# tvbgone3.net
KiCad netlist of a schematic drawn in EAGLE
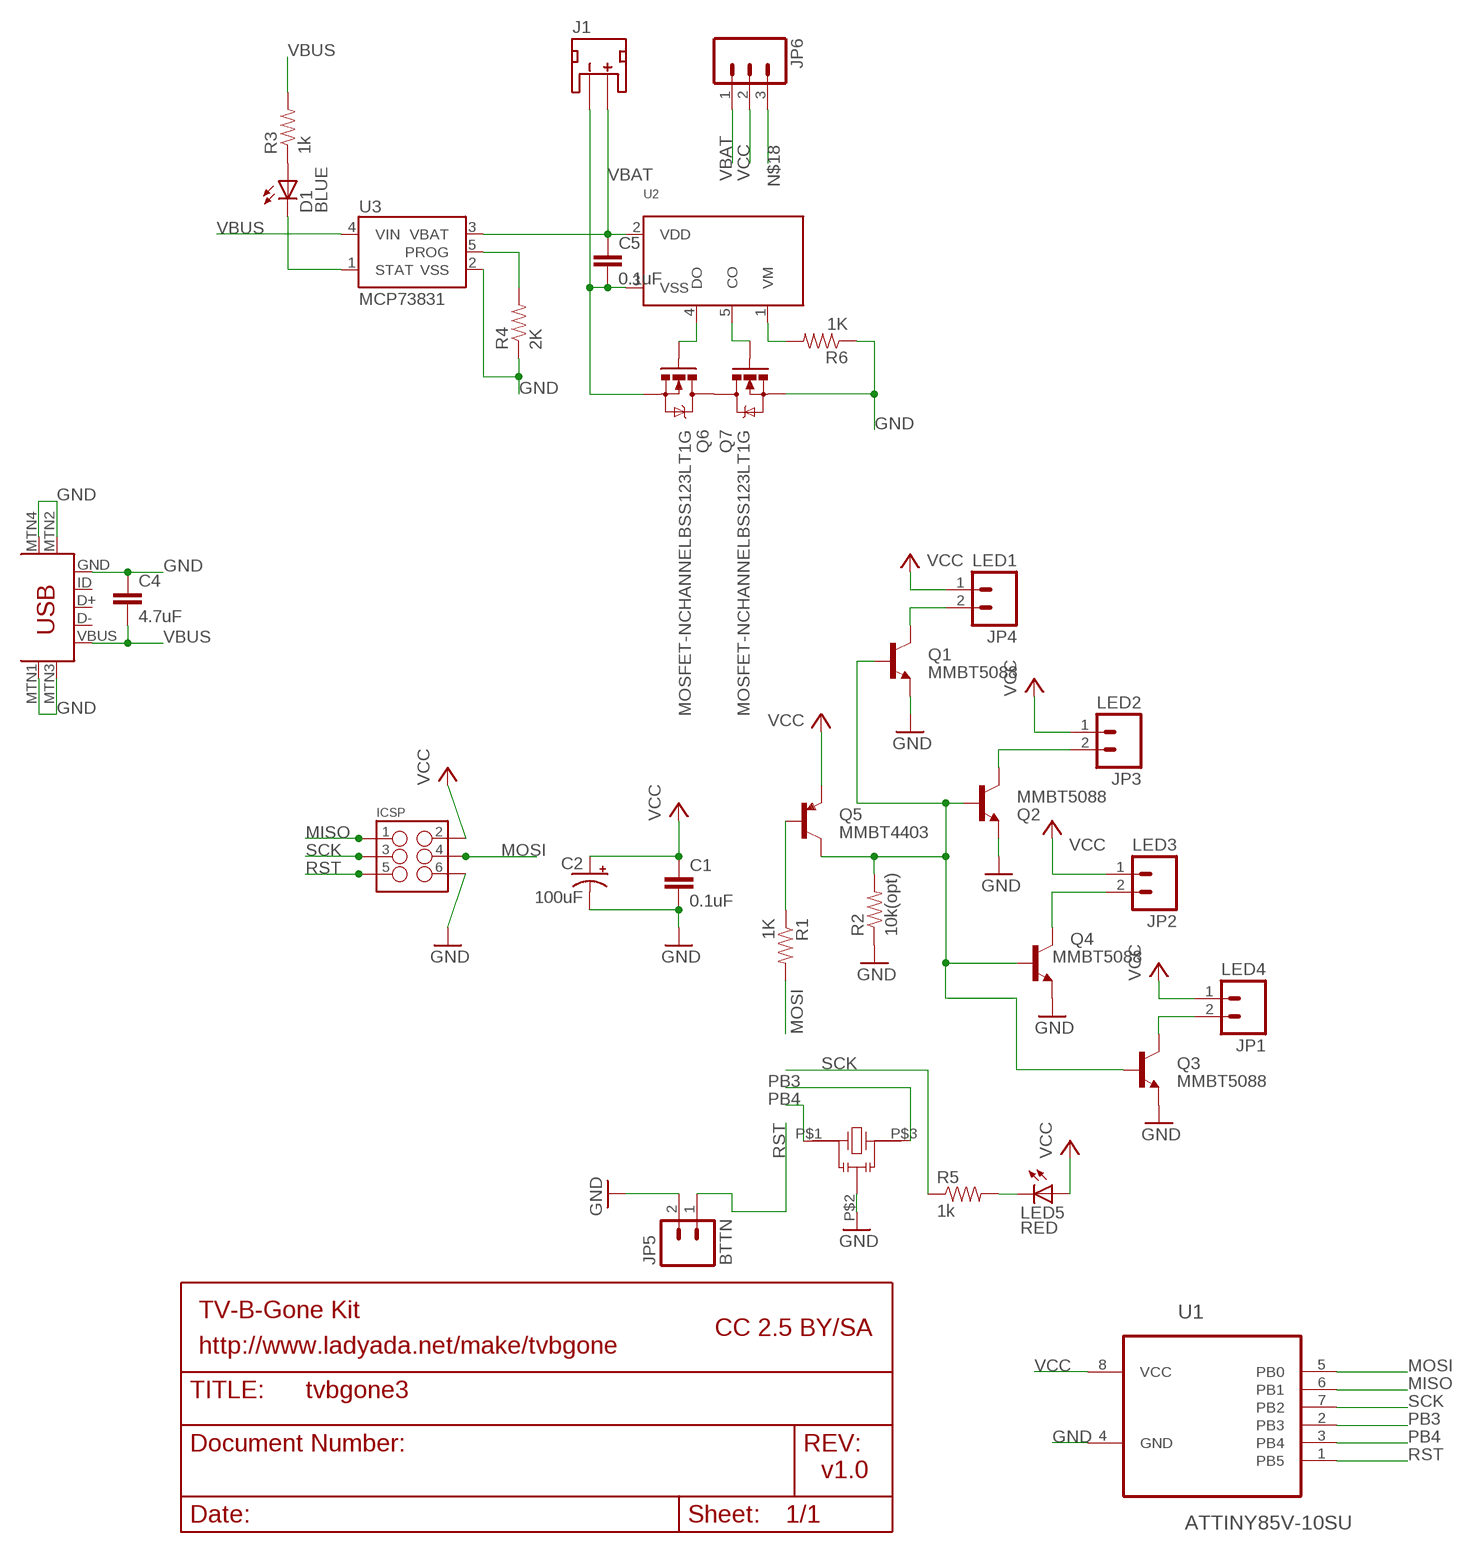
[diagram p0: schematic, sheet 1]

(export (version "E")
  (design (tool "Eeschema 10.0.6"))
  (components
    (comp (ref "C1")
      (value "0.1uF")
      (footprint "eagle-import:0603-CAP")
      (libsource (lib "eagle-import") (part "0.1UF-25V-5%(0603)"))
    )
    (comp (ref "C2")
      (value "100uF")
      (footprint "eagle-import:PANASONIC_C")
      (libsource (lib "eagle-import") (part "CAP_POLC"))
    )
    (comp (ref "C4")
      (value "4.7uF")
      (footprint "eagle-import:0603-CAP")
      (libsource (lib "eagle-import") (part "0.22UF50V-20%,+80%(0603)"))
    )
    (comp (ref "C5")
      (value "0.1uF")
      (footprint "eagle-import:0603-CAP")
      (libsource (lib "eagle-import") (part "0.22UF50V-20%,+80%(0603)"))
    )
    (comp (ref "D1")
      (value "BLUE")
      (footprint "eagle-import:LED-0603")
      (libsource (lib "eagle-import") (part "LED-BLUE0603"))
    )
    (comp (ref "ICSP")
      (value "M03X2SMT")
      (footprint "eagle-import:2X3_SMT_POSTS")
      (libsource (lib "eagle-import") (part "M03X2SMT"))
    )
    (comp (ref "J1")
      (value "JST_2MM_MALE")
      (footprint "eagle-import:JST-2-SMD")
      (libsource (lib "eagle-import") (part "JST_2MM_MALE"))
    )
    (comp (ref "JP1")
      (value "LED4")
      (footprint "eagle-import:1X02_LONGPADS")
      (libsource (lib "eagle-import") (part "M02PTH3"))
    )
    (comp (ref "JP2")
      (value "LED3")
      (footprint "eagle-import:1X02_LONGPADS")
      (libsource (lib "eagle-import") (part "M02PTH3"))
    )
    (comp (ref "JP3")
      (value "LED2")
      (footprint "eagle-import:1X02_LONGPADS")
      (libsource (lib "eagle-import") (part "M02PTH3"))
    )
    (comp (ref "JP4")
      (value "LED1")
      (footprint "eagle-import:1X02_LONGPADS")
      (libsource (lib "eagle-import") (part "M02PTH3"))
    )
    (comp (ref "JP5")
      (value "BTTN")
      (footprint "eagle-import:1X02_LONGPADS")
      (libsource (lib "eagle-import") (part "M02PTH3"))
    )
    (comp (ref "JP6")
      (value "M03SMD_RA_MALE")
      (footprint "eagle-import:1X03_SMD_RA_MALE")
      (libsource (lib "eagle-import") (part "M03SMD_RA_MALE"))
    )
    (comp (ref "LED5")
      (value "RED")
      (footprint "eagle-import:LED-0603")
      (libsource (lib "eagle-import") (part "LED0603"))
    )
    (comp (ref "Q1")
      (value "MMBT5088")
      (footprint "eagle-import:SOT23")
      (libsource (lib "eagle-import") (part "TRANSISTOR_NPNMMBT5088"))
    )
    (comp (ref "Q2")
      (value "MMBT5088")
      (footprint "eagle-import:SOT23")
      (libsource (lib "eagle-import") (part "TRANSISTOR_NPNMMBT5088"))
    )
    (comp (ref "Q3")
      (value "MMBT5088")
      (footprint "eagle-import:SOT23")
      (libsource (lib "eagle-import") (part "TRANSISTOR_NPNMMBT5088"))
    )
    (comp (ref "Q4")
      (value "MMBT5088")
      (footprint "eagle-import:SOT23")
      (libsource (lib "eagle-import") (part "TRANSISTOR_NPNMMBT5088"))
    )
    (comp (ref "Q5")
      (value "MMBT4403")
      (footprint "eagle-import:SOT23")
      (libsource (lib "eagle-import") (part "TRANSISTOR_PNPMMBT4403"))
    )
    (comp (ref "Q6")
      (value "MOSFET-NCHANNELBSS123LT1G")
      (footprint "eagle-import:SOT23")
      (libsource (lib "eagle-import") (part "MOSFET-NCHANNELBSS123LT1G"))
    )
    (comp (ref "Q7")
      (value "MOSFET-NCHANNELBSS123LT1G")
      (footprint "eagle-import:SOT23")
      (libsource (lib "eagle-import") (part "MOSFET-NCHANNELBSS123LT1G"))
    )
    (comp (ref "R1")
      (value "1K")
      (footprint "eagle-import:0603-RES")
      (libsource (lib "eagle-import") (part "2MOHMS-1/10W-1%(0603)"))
    )
    (comp (ref "R2")
      (value "10k(opt)")
      (footprint "eagle-import:0603-RES")
      (libsource (lib "eagle-import") (part "2MOHMS-1/10W-1%(0603)"))
    )
    (comp (ref "R3")
      (value "1k")
      (footprint "eagle-import:0603-RES")
      (libsource (lib "eagle-import") (part "3.3MOHM-1/10W-1%(0603)"))
    )
    (comp (ref "R4")
      (value "2K")
      (footprint "eagle-import:0603-RES")
      (libsource (lib "eagle-import") (part "3.3MOHM-1/10W-1%(0603)"))
    )
    (comp (ref "R5")
      (value "1k")
      (footprint "eagle-import:0603-RES")
      (libsource (lib "eagle-import") (part "2MOHMS-1/10W-1%(0603)"))
    )
    (comp (ref "R6")
      (value "1K")
      (footprint "eagle-import:0603-RES")
      (libsource (lib "eagle-import") (part "3.3MOHM-1/10W-1%(0603)"))
    )
    (comp (ref "U$1")
      (value "CTSCE8M_00G52")
      (footprint "eagle-import:CSTCE")
      (libsource (lib "eagle-import") (part "CTSCE8M_00G52"))
    )
    (comp (ref "U$2")
      (value "USB-MINIB-5PIN")
      (footprint "eagle-import:USB-MINIB")
      (libsource (lib "eagle-import") (part "USB-MINIB-5PIN"))
    )
    (comp (ref "U1")
      (value "ATTINY85V-10SU")
      (footprint "eagle-import:SOIC127P798X216-8N")
      (libsource (lib "eagle-import") (part "ATTINY85V-10SU"))
    )
    (comp (ref "U2")
      (value "S-8241")
      (footprint "eagle-import:SOT23-5L")
      (libsource (lib "eagle-import") (part "S-8241"))
    )
    (comp (ref "U3")
      (value "MCP73831")
      (footprint "eagle-import:SOT23-5")
      (libsource (lib "eagle-import") (part "MCP73831"))
    )
  )
  (nets
    (net (code "1") (name "/MISO") (class "Default")
      (node (ref "ICSP") (pin "1") (pinfunction "1_1") (pintype "bidirectional"))
      (node (ref "U1") (pin "6") (pinfunction "PB1_6") (pintype "bidirectional"))
    )
    (net (code "2") (name "/MOSI") (class "Default")
      (node (ref "ICSP") (pin "4") (pinfunction "4_4") (pintype "bidirectional"))
      (node (ref "R1") (pin "2") (pinfunction "2_2") (pintype "passive"))
      (node (ref "U1") (pin "5") (pinfunction "PB0_5") (pintype "bidirectional"))
    )
    (net (code "3") (name "/N$18") (class "Default")
      (node (ref "JP6") (pin "3") (pinfunction "3_3") (pintype "passive"))
    )
    (net (code "4") (name "/PB3") (class "Default")
      (node (ref "U$1") (pin "P$3") (pinfunction "P$3_P$3") (pintype "bidirectional"))
      (node (ref "U1") (pin "2") (pinfunction "PB3_2") (pintype "bidirectional"))
    )
    (net (code "5") (name "/PB4") (class "Default")
      (node (ref "U$1") (pin "P$1") (pinfunction "P$1_P$1") (pintype "bidirectional"))
      (node (ref "U1") (pin "3") (pinfunction "PB4_3") (pintype "bidirectional"))
    )
    (net (code "6") (name "/RST") (class "Default")
      (node (ref "ICSP") (pin "5") (pinfunction "5_5") (pintype "bidirectional"))
      (node (ref "JP5") (pin "1") (pinfunction "1_1") (pintype "passive"))
      (node (ref "U1") (pin "1") (pinfunction "PB5_1") (pintype "bidirectional"))
    )
    (net (code "7") (name "/SCK") (class "Default")
      (node (ref "ICSP") (pin "3") (pinfunction "3_3") (pintype "bidirectional"))
      (node (ref "R5") (pin "1") (pinfunction "1_1") (pintype "passive"))
      (node (ref "U1") (pin "7") (pinfunction "PB2_7") (pintype "bidirectional"))
    )
    (net (code "8") (name "/VBAT") (class "Default")
      (node (ref "C5") (pin "1") (pinfunction "1_1") (pintype "passive"))
      (node (ref "J1") (pin "2") (pinfunction "+_2") (pintype "bidirectional"))
      (node (ref "JP6") (pin "1") (pinfunction "1_1") (pintype "passive"))
      (node (ref "U2") (pin "2") (pinfunction "VDD_2") (pintype "power_in"))
      (node (ref "U3") (pin "3") (pinfunction "VBAT_3") (pintype "power_in"))
    )
    (net (code "9") (name "/VBUS") (class "Default")
      (node (ref "C4") (pin "2") (pinfunction "2_2") (pintype "passive"))
      (node (ref "R3") (pin "2") (pinfunction "2_2") (pintype "passive"))
      (node (ref "U$2") (pin "VBUS") (pinfunction "VBUS_VBUS") (pintype "bidirectional"))
      (node (ref "U3") (pin "4") (pinfunction "VIN_4") (pintype "power_in"))
    )
    (net (code "10") (name "GND") (class "Default")
      (node (ref "C1") (pin "2") (pinfunction "2_2") (pintype "passive"))
      (node (ref "C2") (pin "-") (pinfunction "-_-") (pintype "passive"))
      (node (ref "C4") (pin "1") (pinfunction "1_1") (pintype "passive"))
      (node (ref "ICSP") (pin "6") (pinfunction "6_6") (pintype "bidirectional"))
      (node (ref "JP5") (pin "2") (pinfunction "2_2") (pintype "passive"))
      (node (ref "Q1") (pin "2") (pinfunction "E_2") (pintype "passive"))
      (node (ref "Q2") (pin "2") (pinfunction "E_2") (pintype "passive"))
      (node (ref "Q3") (pin "2") (pinfunction "E_2") (pintype "passive"))
      (node (ref "Q4") (pin "2") (pinfunction "E_2") (pintype "passive"))
      (node (ref "Q7") (pin "2") (pinfunction "S_2") (pintype "passive"))
      (node (ref "R2") (pin "1") (pinfunction "1_1") (pintype "passive"))
      (node (ref "R4") (pin "1") (pinfunction "1_1") (pintype "passive"))
      (node (ref "R6") (pin "1") (pinfunction "1_1") (pintype "passive"))
      (node (ref "U$1") (pin "P$2") (pinfunction "P$2_P$2") (pintype "bidirectional"))
      (node (ref "U$2") (pin "GND") (pinfunction "GND_GND") (pintype "bidirectional"))
      (node (ref "U$2") (pin "MTN1") (pinfunction "MTN2_MTN1") (pintype "bidirectional"))
      (node (ref "U$2") (pin "MTN2") (pinfunction "MTN3_MTN2") (pintype "bidirectional"))
      (node (ref "U$2") (pin "MTN3") (pinfunction "MTN1_MTN3") (pintype "bidirectional"))
      (node (ref "U$2") (pin "MTN4") (pinfunction "MTN4_MTN4") (pintype "bidirectional"))
      (node (ref "U1") (pin "4") (pinfunction "GND_4") (pintype "passive"))
      (node (ref "U3") (pin "2") (pinfunction "VSS_2") (pintype "power_in"))
    )
    (net (code "11") (name "Net-(D1-PadA)") (class "Default")
      (node (ref "D1") (pin "A") (pinfunction "A_A") (pintype "passive"))
      (node (ref "R3") (pin "1") (pinfunction "1_1") (pintype "passive"))
    )
    (net (code "12") (name "Net-(J1--)") (class "Default")
      (node (ref "C5") (pin "2") (pinfunction "2_2") (pintype "passive"))
      (node (ref "J1") (pin "1") (pinfunction "-_1") (pintype "bidirectional"))
      (node (ref "Q6") (pin "2") (pinfunction "S_2") (pintype "passive"))
      (node (ref "U2") (pin "3") (pinfunction "VSS_3") (pintype "power_in"))
    )
    (net (code "13") (name "Net-(LED5-PadC)") (class "Default")
      (node (ref "LED5") (pin "C") (pinfunction "C_C") (pintype "passive"))
      (node (ref "R5") (pin "2") (pinfunction "2_2") (pintype "passive"))
    )
    (net (code "14") (name "Net-(Q1-B)") (class "Default")
      (node (ref "Q1") (pin "1") (pinfunction "B_1") (pintype "passive"))
      (node (ref "Q2") (pin "1") (pinfunction "B_1") (pintype "passive"))
      (node (ref "Q3") (pin "1") (pinfunction "B_1") (pintype "passive"))
      (node (ref "Q4") (pin "1") (pinfunction "B_1") (pintype "passive"))
      (node (ref "Q5") (pin "3") (pinfunction "C_3") (pintype "passive"))
      (node (ref "R2") (pin "2") (pinfunction "2_2") (pintype "passive"))
    )
    (net (code "15") (name "Net-(Q1-C)") (class "Default")
      (node (ref "JP4") (pin "2") (pinfunction "2_2") (pintype "passive"))
      (node (ref "Q1") (pin "3") (pinfunction "C_3") (pintype "passive"))
    )
    (net (code "16") (name "Net-(Q2-C)") (class "Default")
      (node (ref "JP3") (pin "2") (pinfunction "2_2") (pintype "passive"))
      (node (ref "Q2") (pin "3") (pinfunction "C_3") (pintype "passive"))
    )
    (net (code "17") (name "Net-(Q3-C)") (class "Default")
      (node (ref "JP1") (pin "2") (pinfunction "2_2") (pintype "passive"))
      (node (ref "Q3") (pin "3") (pinfunction "C_3") (pintype "passive"))
    )
    (net (code "18") (name "Net-(Q4-C)") (class "Default")
      (node (ref "JP2") (pin "2") (pinfunction "2_2") (pintype "passive"))
      (node (ref "Q4") (pin "3") (pinfunction "C_3") (pintype "passive"))
    )
    (net (code "19") (name "Net-(Q5-B)") (class "Default")
      (node (ref "Q5") (pin "1") (pinfunction "B_1") (pintype "passive"))
      (node (ref "R1") (pin "1") (pinfunction "1_1") (pintype "passive"))
    )
    (net (code "20") (name "Net-(Q6-D)") (class "Default")
      (node (ref "Q6") (pin "3") (pinfunction "D_3") (pintype "passive"))
      (node (ref "Q7") (pin "3") (pinfunction "D_3") (pintype "passive"))
    )
    (net (code "21") (name "Net-(Q6-G)") (class "Default")
      (node (ref "Q6") (pin "1") (pinfunction "G_1") (pintype "passive"))
      (node (ref "U2") (pin "4") (pinfunction "DO_4") (pintype "power_in"))
    )
    (net (code "22") (name "Net-(Q7-G)") (class "Default")
      (node (ref "Q7") (pin "1") (pinfunction "G_1") (pintype "passive"))
      (node (ref "U2") (pin "5") (pinfunction "CO_5") (pintype "bidirectional"))
    )
    (net (code "23") (name "Net-(U2-VM)") (class "Default")
      (node (ref "R6") (pin "2") (pinfunction "2_2") (pintype "passive"))
      (node (ref "U2") (pin "1") (pinfunction "VM_1") (pintype "power_in"))
    )
    (net (code "24") (name "Net-(U3-PROG)") (class "Default")
      (node (ref "R4") (pin "2") (pinfunction "2_2") (pintype "passive"))
      (node (ref "U3") (pin "5") (pinfunction "PROG_5") (pintype "input"))
    )
    (net (code "25") (name "Net-(U3-STAT)") (class "Default")
      (node (ref "D1") (pin "C") (pinfunction "C_C") (pintype "passive"))
      (node (ref "U3") (pin "1") (pinfunction "STAT_1") (pintype "output"))
    )
    (net (code "26") (name "VCC") (class "Default")
      (node (ref "C1") (pin "1") (pinfunction "1_1") (pintype "passive"))
      (node (ref "C2") (pin "+") (pinfunction "+_+") (pintype "passive"))
      (node (ref "ICSP") (pin "2") (pinfunction "2_2") (pintype "bidirectional"))
      (node (ref "JP1") (pin "1") (pinfunction "1_1") (pintype "passive"))
      (node (ref "JP2") (pin "1") (pinfunction "1_1") (pintype "passive"))
      (node (ref "JP3") (pin "1") (pinfunction "1_1") (pintype "passive"))
      (node (ref "JP4") (pin "1") (pinfunction "1_1") (pintype "passive"))
      (node (ref "JP6") (pin "2") (pinfunction "2_2") (pintype "passive"))
      (node (ref "LED5") (pin "A") (pinfunction "A_A") (pintype "passive"))
      (node (ref "Q5") (pin "2") (pinfunction "E_2") (pintype "passive"))
      (node (ref "U1") (pin "8") (pinfunction "VCC_8") (pintype "power_in"))
    )
    (net (code "27") (name "unconnected-(J1-PAD1-PadNC1)") (class "Default")
      (node (ref "J1") (pin "NC1") (pinfunction "PAD1_NC1") (pintype "bidirectional"))
    )
    (net (code "28") (name "unconnected-(J1-PAD2-PadNC2)") (class "Default")
      (node (ref "J1") (pin "NC2") (pinfunction "PAD2_NC2") (pintype "bidirectional"))
    )
    (net (code "29") (name "unconnected-(U$2-PadD+)") (class "Default")
      (node (ref "U$2") (pin "D+") (pinfunction "D+_D+") (pintype "bidirectional"))
    )
    (net (code "30") (name "unconnected-(U$2-PadD-)") (class "Default")
      (node (ref "U$2") (pin "D-") (pinfunction "D-_D-") (pintype "bidirectional"))
    )
    (net (code "31") (name "unconnected-(U$2-PadID)") (class "Default")
      (node (ref "U$2") (pin "ID") (pinfunction "ID_ID") (pintype "bidirectional"))
    )
  )
)
